# AUDIO_CODEC.net
KiCad netlist of a schematic drawn in Altium Designer
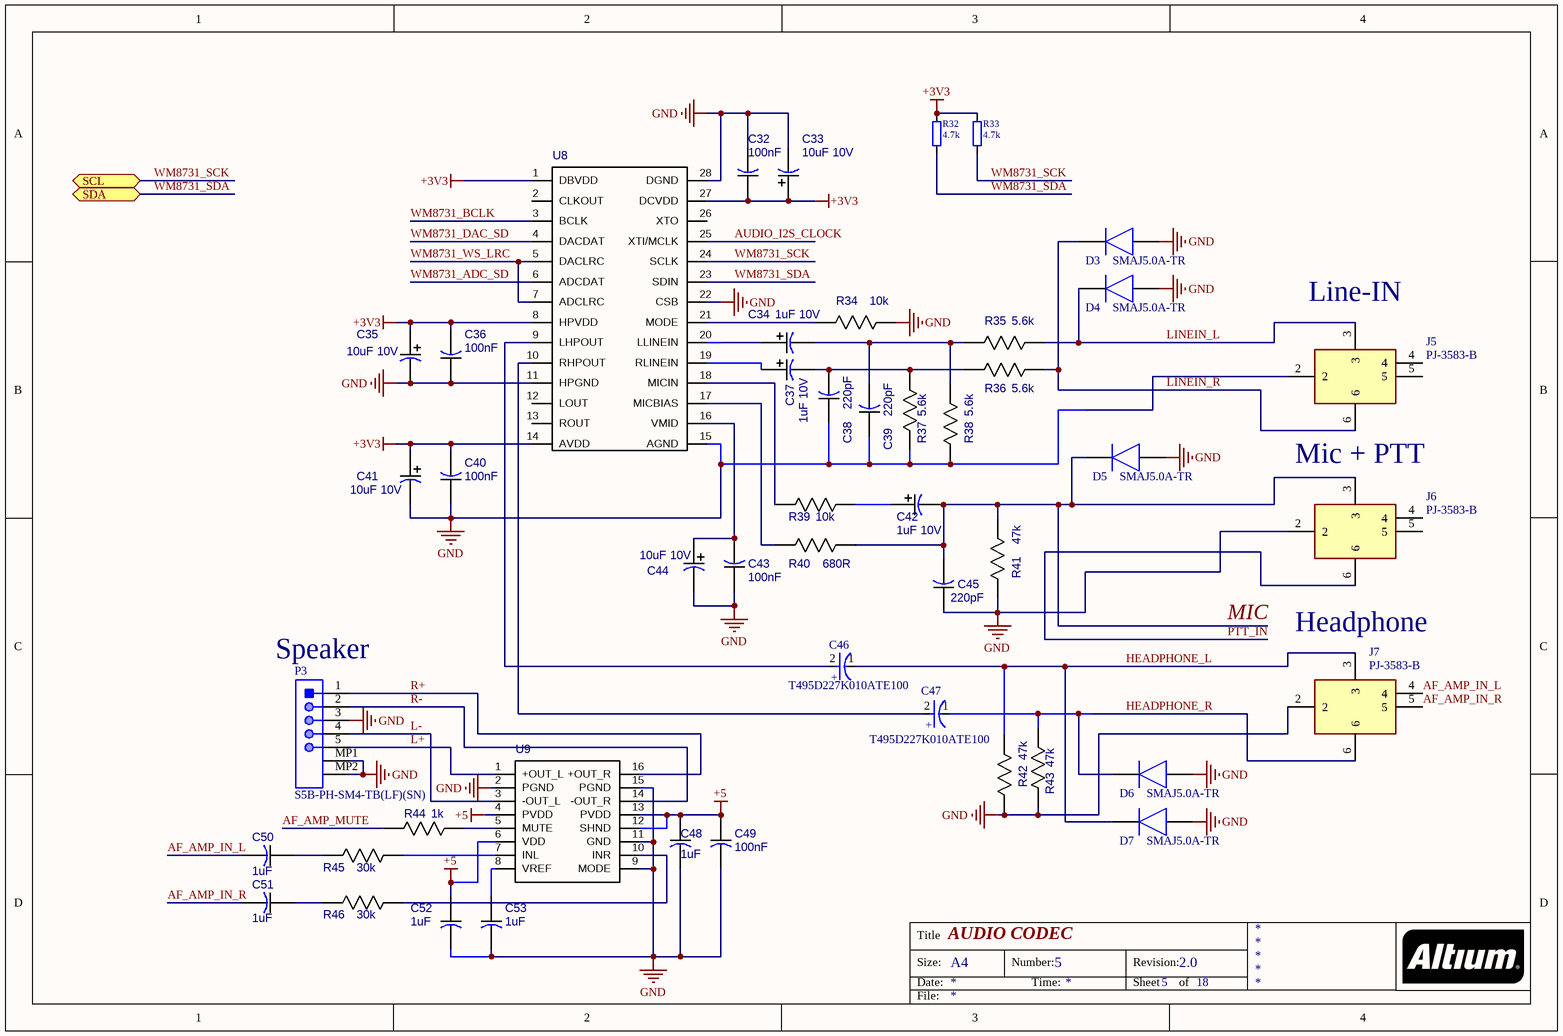
[diagram p0: AUDIO CODEC.SchDoc]

(export (version "E")
  (design (tool "Eeschema 10.0.6"))
  (components
    (comp (ref "C32")
      (value "100nF")
      (footprint "CAP_0805")
      (description "CAP_0805")
      (libsource (lib "*") (part "CAP_0805"))
    )
    (comp (ref "C33")
      (value "10uF 10V")
      (footprint "CAPAE_4.3x4.3h5.4")
      (description "CAPAE_4.3x4.3h5.4")
      (libsource (lib "*") (part "CAPAE_4.3x4.3h5.4"))
    )
    (comp (ref "C34")
      (value "1uF 10V")
      (footprint "CAPAE_4.3x4.3h5.4")
      (description "CAPAE_4.3x4.3h5.4")
      (libsource (lib "*") (part "CAPAE_4.3x4.3h5.4"))
    )
    (comp (ref "C35")
      (value "10uF 10V")
      (footprint "CAPAE_4.3x4.3h5.4")
      (description "CAPAE_4.3x4.3h5.4")
      (libsource (lib "*") (part "CAPAE_4.3x4.3h5.4"))
    )
    (comp (ref "C36")
      (value "100nF")
      (footprint "CAP_0805")
      (description "CAP_0805")
      (libsource (lib "*") (part "CAP_0805"))
    )
    (comp (ref "C37")
      (value "1uF 10V")
      (footprint "CAPAE_4.3x4.3h5.4")
      (description "CAPAE_4.3x4.3h5.4")
      (libsource (lib "*") (part "CAPAE_4.3x4.3h5.4"))
    )
    (comp (ref "C38")
      (value "220pF")
      (footprint "CAP_0805")
      (description "CAP_0805")
      (libsource (lib "*") (part "CAP_0805"))
    )
    (comp (ref "C39")
      (value "220pF")
      (footprint "CAP_0805")
      (description "CAP_0805")
      (libsource (lib "*") (part "CAP_0805"))
    )
    (comp (ref "C40")
      (value "100nF")
      (footprint "CAP_0805")
      (description "CAP_0805")
      (libsource (lib "*") (part "CAP_0805"))
    )
    (comp (ref "C41")
      (value "10uF 10V")
      (footprint "CAPAE_4.3x4.3h5.4")
      (description "CAPAE_4.3x4.3h5.4")
      (libsource (lib "*") (part "CAPAE_4.3x4.3h5.4"))
    )
    (comp (ref "C42")
      (value "1uF 10V")
      (footprint "CAPAE_4.3x4.3h5.4")
      (description "CAPAE_4.3x4.3h5.4")
      (libsource (lib "*") (part "CAPAE_4.3x4.3h5.4"))
    )
    (comp (ref "C43")
      (value "100nF")
      (footprint "CAP_0805")
      (description "CAP_0805")
      (libsource (lib "*") (part "CAP_0805"))
    )
    (comp (ref "C44")
      (value "10uF 10V")
      (footprint "CAPAE_4.3x4.3h5.4")
      (description "CAPAE_4.3x4.3h5.4")
      (libsource (lib "*") (part "CAPAE_4.3x4.3h5.4"))
    )
    (comp (ref "C45")
      (value "220pF")
      (footprint "CAP_0805")
      (description "CAP_0805")
      (libsource (lib "*") (part "CAP_0805"))
    )
    (comp (ref "C46")
      (value "T495D227K010ATE100")
      (footprint "FP-T495D227K010ATE100-MFG")
      (description "CAP TANT 220UF 10% 10V 2917")
      (fields (field (name "TOLERANCE") "10%") (field (name "VOLTAGE") "10V"))
      (libsource (lib "Altium Content Vault") (part "203bc49f2ac43e59fd269a8c329ed05"))
    )
    (comp (ref "C47")
      (value "T495D227K010ATE100")
      (footprint "FP-T495D227K010ATE100-MFG")
      (description "CAP TANT 220UF 10% 10V 2917")
      (fields (field (name "TOLERANCE") "10%") (field (name "VOLTAGE") "10V"))
      (libsource (lib "Altium Content Vault") (part "203bc49f2ac43e59fd269a8c329ed05"))
    )
    (comp (ref "C48")
      (value "1uF")
      (footprint "CAP_0805")
      (description "CAP_0805")
      (libsource (lib "*") (part "CAP_0805"))
    )
    (comp (ref "C49")
      (value "100nF")
      (footprint "CAP_0805")
      (description "CAP_0805")
      (libsource (lib "*") (part "CAP_0805"))
    )
    (comp (ref "C50")
      (value "1uF")
      (footprint "CAP_0805")
      (description "CAP_0805")
      (libsource (lib "*") (part "CAP_0805"))
    )
    (comp (ref "C51")
      (value "1uF")
      (footprint "CAP_0805")
      (description "CAP_0805")
      (libsource (lib "*") (part "CAP_0805"))
    )
    (comp (ref "C52")
      (value "1uF")
      (footprint "CAP_0805")
      (description "CAP_0805")
      (libsource (lib "*") (part "CAP_0805"))
    )
    (comp (ref "C53")
      (value "1uF")
      (footprint "CAP_0805")
      (description "CAP_0805")
      (libsource (lib "*") (part "CAP_0805"))
    )
    (comp (ref "D3")
      (value "SMAJ5.0A-TR")
      (footprint "SMBJ36CATR")
      (description "Diode")
      (fields
        (field (name "MANUFACTURER_PART_NUMBER") "SMLVT3V3")
        (field (name "MOUSER PART NUMBER") "511-SMLVT3V3")
      )
      (libsource (lib "FRONT-UNIT-7") (part "SMLVT3V3"))
    )
    (comp (ref "D4")
      (value "SMAJ5.0A-TR")
      (footprint "SMBJ36CATR")
      (description "Diode")
      (fields
        (field (name "MANUFACTURER_PART_NUMBER") "SMLVT3V3")
        (field (name "MOUSER PART NUMBER") "511-SMLVT3V3")
      )
      (libsource (lib "FRONT-UNIT-7") (part "SMLVT3V3"))
    )
    (comp (ref "D5")
      (value "SMAJ5.0A-TR")
      (footprint "SMBJ36CATR")
      (description "Diode")
      (fields
        (field (name "MANUFACTURER_PART_NUMBER") "SMLVT3V3")
        (field (name "MOUSER PART NUMBER") "511-SMLVT3V3")
      )
      (libsource (lib "FRONT-UNIT-7") (part "SMLVT3V3"))
    )
    (comp (ref "D6")
      (value "SMAJ5.0A-TR")
      (footprint "SMBJ36CATR")
      (description "Diode")
      (fields
        (field (name "MANUFACTURER_PART_NUMBER") "SMLVT3V3")
        (field (name "MOUSER PART NUMBER") "511-SMLVT3V3")
      )
      (libsource (lib "FRONT-UNIT-7") (part "SMLVT3V3"))
    )
    (comp (ref "D7")
      (value "SMAJ5.0A-TR")
      (footprint "SMBJ36CATR")
      (description "Diode")
      (fields
        (field (name "MANUFACTURER_PART_NUMBER") "SMLVT3V3")
        (field (name "MOUSER PART NUMBER") "511-SMLVT3V3")
      )
      (libsource (lib "FRONT-UNIT-7") (part "SMLVT3V3"))
    )
    (comp (ref "J5")
      (value "PJ-3583-B")
      (footprint "SamacSys:PJ3583B")
      (description "Connector")
      (libsource (lib "*") (part "PJ-3583-B"))
    )
    (comp (ref "J6")
      (value "PJ-3583-B")
      (footprint "SamacSys:PJ3583B")
      (description "Connector")
      (libsource (lib "*") (part "PJ-3583-B"))
    )
    (comp (ref "J7")
      (value "PJ-3583-B")
      (footprint "SamacSys:PJ3583B")
      (description "Connector")
      (libsource (lib "*") (part "PJ-3583-B"))
    )
    (comp (ref "P3")
      (value "S5B-PH-SM4-TB(LF)(SN)")
      (footprint "JST-S5B-PH-SM4-TB_V")
      (description "Male Header, Pitch 2 mm, 1 x 5 Position, Height 5.5 mm, -25 to 85 degC, RoHS, Tape and Reel")
      (fields (field (name "MANUFACTURER") "JST"))
      (libsource (lib "Altium Content Vault") (part "CN-1P-2M-R5"))
    )
    (comp (ref "R32")
      (value "4.7k")
      (footprint "R-0805")
      (description "Chip Resistor")
      (fields (field (name "MANUFACTURER") "Yageo/Phycomp"))
      (libsource (lib "Hristo") (part "RES semi"))
    )
    (comp (ref "R33")
      (value "4.7k")
      (footprint "R-0805")
      (description "Chip Resistor")
      (fields (field (name "MANUFACTURER") "Yageo/Phycomp"))
      (libsource (lib "Hristo") (part "RES semi"))
    )
    (comp (ref "R34")
      (value "10k")
      (footprint "RES_0805")
      (description "RES_0805")
      (libsource (lib "*") (part "RES_0805"))
    )
    (comp (ref "R35")
      (value "5.6k")
      (footprint "RES_0805")
      (description "RES_0805")
      (libsource (lib "*") (part "RES_0805"))
    )
    (comp (ref "R36")
      (value "5.6k")
      (footprint "RES_0805")
      (description "RES_0805")
      (libsource (lib "*") (part "RES_0805"))
    )
    (comp (ref "R37")
      (value "5.6k")
      (footprint "RES_0805")
      (description "RES_0805")
      (libsource (lib "*") (part "RES_0805"))
    )
    (comp (ref "R38")
      (value "5.6k")
      (footprint "RES_0805")
      (description "RES_0805")
      (libsource (lib "*") (part "RES_0805"))
    )
    (comp (ref "R39")
      (value "10k")
      (footprint "RES_0805")
      (description "RES_0805")
      (libsource (lib "*") (part "RES_0805"))
    )
    (comp (ref "R40")
      (value "680R")
      (footprint "RES_0805")
      (description "RES_0805")
      (libsource (lib "*") (part "RES_0805"))
    )
    (comp (ref "R41")
      (value "47k")
      (footprint "RES_0805")
      (description "RES_0805")
      (libsource (lib "*") (part "RES_0805"))
    )
    (comp (ref "R42")
      (value "47k")
      (footprint "RES_0805")
      (description "RES_0805")
      (libsource (lib "*") (part "RES_0805"))
    )
    (comp (ref "R43")
      (value "47k")
      (footprint "RES_0805")
      (description "RES_0805")
      (libsource (lib "*") (part "RES_0805"))
    )
    (comp (ref "R44")
      (value "1k")
      (footprint "RES_0805")
      (description "RES_0805")
      (libsource (lib "*") (part "RES_0805"))
    )
    (comp (ref "R45")
      (value "30k")
      (footprint "RES_0805")
      (description "RES_0805")
      (libsource (lib "*") (part "RES_0805"))
    )
    (comp (ref "R46")
      (value "30k")
      (footprint "RES_0805")
      (description "RES_0805")
      (libsource (lib "*") (part "RES_0805"))
    )
    (comp (ref "U8") (value "WM8731") (footprint "WM8731") (libsource (lib "FRONT-UNIT-7") (part "WM8731")))
    (comp (ref "U9")
      (value "PAM8406")
      (footprint "PAM8403")
      (libsource (lib "FRONT-UNIT-7") (part "PAM8406"))
    )
  )
  (nets
    (net (code "1") (name "+3V3") (class "Default")
      (node (ref "C32") (pin "1") (pinfunction "1_1") (pintype "passive"))
      (node (ref "C33") (pin "1") (pinfunction "PLUS_1") (pintype "passive"))
      (node (ref "C35") (pin "1") (pinfunction "PLUS_1") (pintype "passive"))
      (node (ref "C36") (pin "2") (pinfunction "2_2") (pintype "passive"))
      (node (ref "C40") (pin "2") (pinfunction "2_2") (pintype "passive"))
      (node (ref "C41") (pin "1") (pinfunction "PLUS_1") (pintype "passive"))
      (node (ref "R32") (pin "2") (pinfunction "2_2") (pintype "passive"))
      (node (ref "R33") (pin "2") (pinfunction "2_2") (pintype "passive"))
      (node (ref "U8") (pin "1") (pinfunction "DBVDD_1") (pintype "passive"))
      (node (ref "U8") (pin "14") (pinfunction "AVDD_14") (pintype "passive"))
      (node (ref "U8") (pin "27") (pinfunction "DCVDD_27") (pintype "passive"))
      (node (ref "U8") (pin "8") (pinfunction "HPVDD_8") (pintype "passive"))
    )
    (net (code "2") (name "+5") (class "Default")
      (node (ref "C48") (pin "1") (pinfunction "1_1") (pintype "passive"))
      (node (ref "C49") (pin "1") (pinfunction "1_1") (pintype "passive"))
      (node (ref "C52") (pin "1") (pinfunction "1_1") (pintype "passive"))
      (node (ref "U9") (pin "12") (pinfunction "SHND_12") (pintype "passive"))
      (node (ref "U9") (pin "13") (pinfunction "PVDD_13") (pintype "passive"))
      (node (ref "U9") (pin "4") (pinfunction "PVDD_4") (pintype "passive"))
      (node (ref "U9") (pin "6") (pinfunction "VDD_6") (pintype "passive"))
    )
    (net (code "3") (name "/AF_AMP_IN_L") (class "Default")
      (node (ref "C50") (pin "2") (pinfunction "2_2") (pintype "passive"))
      (node (ref "J7") (pin "4") (pinfunction "4_4") (pintype "passive"))
    )
    (net (code "4") (name "/AF_AMP_IN_R") (class "Default")
      (node (ref "C51") (pin "2") (pinfunction "2_2") (pintype "passive"))
      (node (ref "J7") (pin "5") (pinfunction "5_5") (pintype "passive"))
    )
    (net (code "5") (name "/AF_AMP_MUTE") (class "Default")
      (node (ref "R44") (pin "2") (pinfunction "2_2") (pintype "passive"))
    )
    (net (code "6") (name "/AUDIO_I2S_CLOCK") (class "Default")
      (node (ref "U8") (pin "25") (pinfunction "XTI/MCLK_25") (pintype "passive"))
    )
    (net (code "7") (name "/HEADPHONE_L") (class "Default")
      (node (ref "C46") (pin "1") (pinfunction "C_1") (pintype "passive"))
      (node (ref "D7") (pin "1") (pinfunction "K_1") (pintype "passive"))
      (node (ref "J7") (pin "3") (pinfunction "3_3") (pintype "passive"))
      (node (ref "R42") (pin "2") (pinfunction "2_2") (pintype "passive"))
    )
    (net (code "8") (name "/HEADPHONE_R") (class "Default")
      (node (ref "C47") (pin "1") (pinfunction "C_1") (pintype "passive"))
      (node (ref "D6") (pin "1") (pinfunction "K_1") (pintype "passive"))
      (node (ref "J7") (pin "6") (pinfunction "6_6") (pintype "passive"))
      (node (ref "R43") (pin "2") (pinfunction "2_2") (pintype "passive"))
    )
    (net (code "9") (name "/L+") (class "Default")
      (node (ref "P3") (pin "5") (pinfunction "5_5") (pintype "passive"))
      (node (ref "U9") (pin "1") (pinfunction "+OUT_L_1") (pintype "passive"))
    )
    (net (code "10") (name "/L-") (class "Default")
      (node (ref "P3") (pin "4") (pinfunction "4_4") (pintype "passive"))
      (node (ref "U9") (pin "3") (pinfunction "-OUT_L_3") (pintype "passive"))
    )
    (net (code "11") (name "/LINEIN_L") (class "Default")
      (node (ref "D4") (pin "1") (pinfunction "K_1") (pintype "passive"))
      (node (ref "J5") (pin "3") (pinfunction "3_3") (pintype "passive"))
      (node (ref "R35") (pin "1") (pinfunction "1_1") (pintype "passive"))
    )
    (net (code "12") (name "/LINEIN_R") (class "Default")
      (node (ref "D3") (pin "1") (pinfunction "K_1") (pintype "passive"))
      (node (ref "J5") (pin "6") (pinfunction "6_6") (pintype "passive"))
      (node (ref "R36") (pin "1") (pinfunction "1_1") (pintype "passive"))
    )
    (net (code "13") (name "/MIC") (class "Default")
      (node (ref "C42") (pin "2") (pinfunction "MINUS_2") (pintype "passive"))
      (node (ref "C45") (pin "2") (pinfunction "2_2") (pintype "passive"))
      (node (ref "D5") (pin "1") (pinfunction "K_1") (pintype "passive"))
      (node (ref "J6") (pin "3") (pinfunction "3_3") (pintype "passive"))
      (node (ref "R40") (pin "1") (pinfunction "1_1") (pintype "passive"))
      (node (ref "R41") (pin "2") (pinfunction "2_2") (pintype "passive"))
    )
    (net (code "14") (name "/PTT_IN") (class "Default")
      (node (ref "J6") (pin "6") (pinfunction "6_6") (pintype "passive"))
    )
    (net (code "15") (name "/R+") (class "Default")
      (node (ref "P3") (pin "1") (pinfunction "1_1") (pintype "passive"))
      (node (ref "U9") (pin "16") (pinfunction "+OUT_R_16") (pintype "passive"))
    )
    (net (code "16") (name "/R-") (class "Default")
      (node (ref "P3") (pin "2") (pinfunction "2_2") (pintype "passive"))
      (node (ref "U9") (pin "14") (pinfunction "-OUT_R_14") (pintype "passive"))
    )
    (net (code "17") (name "/WM8731_ADC_SD") (class "Default")
      (node (ref "U8") (pin "6") (pinfunction "ADCDAT_6") (pintype "passive"))
    )
    (net (code "18") (name "/WM8731_BCLK") (class "Default")
      (node (ref "U8") (pin "3") (pinfunction "BCLK_3") (pintype "passive"))
    )
    (net (code "19") (name "/WM8731_DAC_SD") (class "Default")
      (node (ref "U8") (pin "4") (pinfunction "DACDAT_4") (pintype "passive"))
    )
    (net (code "20") (name "/WM8731_SCK") (class "Default")
      (node (ref "R33") (pin "1") (pinfunction "1_1") (pintype "passive"))
      (node (ref "U8") (pin "24") (pinfunction "SCLK_24") (pintype "passive"))
    )
    (net (code "21") (name "/WM8731_SDA") (class "Default")
      (node (ref "R32") (pin "1") (pinfunction "1_1") (pintype "passive"))
      (node (ref "U8") (pin "23") (pinfunction "SDIN_23") (pintype "passive"))
    )
    (net (code "22") (name "/WM8731_WS_LRC") (class "Default")
      (node (ref "U8") (pin "5") (pinfunction "DACLRC_5") (pintype "passive"))
      (node (ref "U8") (pin "7") (pinfunction "ADCLRC_7") (pintype "passive"))
    )
    (net (code "23") (name "GND") (class "Default")
      (node (ref "C32") (pin "2") (pinfunction "2_2") (pintype "passive"))
      (node (ref "C33") (pin "2") (pinfunction "MINUS_2") (pintype "passive"))
      (node (ref "C35") (pin "2") (pinfunction "MINUS_2") (pintype "passive"))
      (node (ref "C36") (pin "1") (pinfunction "1_1") (pintype "passive"))
      (node (ref "C38") (pin "1") (pinfunction "1_1") (pintype "passive"))
      (node (ref "C39") (pin "1") (pinfunction "1_1") (pintype "passive"))
      (node (ref "C40") (pin "1") (pinfunction "1_1") (pintype "passive"))
      (node (ref "C41") (pin "2") (pinfunction "MINUS_2") (pintype "passive"))
      (node (ref "C43") (pin "1") (pinfunction "1_1") (pintype "passive"))
      (node (ref "C44") (pin "2") (pinfunction "MINUS_2") (pintype "passive"))
      (node (ref "C45") (pin "1") (pinfunction "1_1") (pintype "passive"))
      (node (ref "C48") (pin "2") (pinfunction "2_2") (pintype "passive"))
      (node (ref "C49") (pin "2") (pinfunction "2_2") (pintype "passive"))
      (node (ref "C52") (pin "2") (pinfunction "2_2") (pintype "passive"))
      (node (ref "C53") (pin "2") (pinfunction "2_2") (pintype "passive"))
      (node (ref "D3") (pin "2") (pinfunction "A_2") (pintype "passive"))
      (node (ref "D4") (pin "2") (pinfunction "A_2") (pintype "passive"))
      (node (ref "D5") (pin "2") (pinfunction "A_2") (pintype "passive"))
      (node (ref "D6") (pin "2") (pinfunction "A_2") (pintype "passive"))
      (node (ref "D7") (pin "2") (pinfunction "A_2") (pintype "passive"))
      (node (ref "J5") (pin "2") (pinfunction "2_2") (pintype "passive"))
      (node (ref "J6") (pin "2") (pinfunction "2_2") (pintype "passive"))
      (node (ref "J7") (pin "2") (pinfunction "2_2") (pintype "passive"))
      (node (ref "P3") (pin "3") (pinfunction "3_3") (pintype "passive"))
      (node (ref "P3") (pin "MP1") (pinfunction "MP1_MP1") (pintype "passive"))
      (node (ref "P3") (pin "MP2") (pinfunction "MP2_MP2") (pintype "passive"))
      (node (ref "R34") (pin "1") (pinfunction "1_1") (pintype "passive"))
      (node (ref "R37") (pin "1") (pinfunction "1_1") (pintype "passive"))
      (node (ref "R38") (pin "1") (pinfunction "1_1") (pintype "passive"))
      (node (ref "R41") (pin "1") (pinfunction "1_1") (pintype "passive"))
      (node (ref "R42") (pin "1") (pinfunction "1_1") (pintype "passive"))
      (node (ref "R43") (pin "1") (pinfunction "1_1") (pintype "passive"))
      (node (ref "U8") (pin "11") (pinfunction "HPGND_11") (pintype "passive"))
      (node (ref "U8") (pin "15") (pinfunction "AGND_15") (pintype "passive"))
      (node (ref "U8") (pin "22") (pinfunction "CSB_22") (pintype "passive"))
      (node (ref "U8") (pin "28") (pinfunction "DGND_28") (pintype "passive"))
      (node (ref "U9") (pin "11") (pinfunction "GND_11") (pintype "passive"))
      (node (ref "U9") (pin "15") (pinfunction "PGND_15") (pintype "passive"))
      (node (ref "U9") (pin "2") (pinfunction "PGND_2") (pintype "passive"))
      (node (ref "U9") (pin "9") (pinfunction "MODE_9") (pintype "passive"))
    )
    (net (code "24") (name "Net-(C34-MINUS)") (class "Default")
      (node (ref "C34") (pin "2") (pinfunction "MINUS_2") (pintype "passive"))
      (node (ref "C39") (pin "2") (pinfunction "2_2") (pintype "passive"))
      (node (ref "R35") (pin "2") (pinfunction "2_2") (pintype "passive"))
      (node (ref "R38") (pin "2") (pinfunction "2_2") (pintype "passive"))
    )
    (net (code "25") (name "Net-(C34-PLUS)") (class "Default")
      (node (ref "C34") (pin "1") (pinfunction "PLUS_1") (pintype "passive"))
      (node (ref "U8") (pin "20") (pinfunction "LLINEIN_20") (pintype "passive"))
    )
    (net (code "26") (name "Net-(C37-MINUS)") (class "Default")
      (node (ref "C37") (pin "2") (pinfunction "MINUS_2") (pintype "passive"))
      (node (ref "C38") (pin "2") (pinfunction "2_2") (pintype "passive"))
      (node (ref "R36") (pin "2") (pinfunction "2_2") (pintype "passive"))
      (node (ref "R37") (pin "2") (pinfunction "2_2") (pintype "passive"))
    )
    (net (code "27") (name "Net-(C37-PLUS)") (class "Default")
      (node (ref "C37") (pin "1") (pinfunction "PLUS_1") (pintype "passive"))
      (node (ref "U8") (pin "19") (pinfunction "RLINEIN_19") (pintype "passive"))
    )
    (net (code "28") (name "Net-(C42-PLUS)") (class "Default")
      (node (ref "C42") (pin "1") (pinfunction "PLUS_1") (pintype "passive"))
      (node (ref "R39") (pin "1") (pinfunction "1_1") (pintype "passive"))
    )
    (net (code "29") (name "Net-(C44-PLUS)") (class "Default")
      (node (ref "C43") (pin "2") (pinfunction "2_2") (pintype "passive"))
      (node (ref "C44") (pin "1") (pinfunction "PLUS_1") (pintype "passive"))
      (node (ref "U8") (pin "16") (pinfunction "VMID_16") (pintype "passive"))
    )
    (net (code "30") (name "Net-(C46-A)") (class "Default")
      (node (ref "C46") (pin "2") (pinfunction "A_2") (pintype "passive"))
      (node (ref "U8") (pin "9") (pinfunction "LHPOUT_9") (pintype "passive"))
    )
    (net (code "31") (name "Net-(C47-A)") (class "Default")
      (node (ref "C47") (pin "2") (pinfunction "A_2") (pintype "passive"))
      (node (ref "U8") (pin "10") (pinfunction "RHPOUT_10") (pintype "passive"))
    )
    (net (code "32") (name "Net-(C50-Pad1)") (class "Default")
      (node (ref "C50") (pin "1") (pinfunction "1_1") (pintype "passive"))
      (node (ref "R45") (pin "2") (pinfunction "2_2") (pintype "passive"))
    )
    (net (code "33") (name "Net-(C51-Pad1)") (class "Default")
      (node (ref "C51") (pin "1") (pinfunction "1_1") (pintype "passive"))
      (node (ref "R46") (pin "2") (pinfunction "2_2") (pintype "passive"))
    )
    (net (code "34") (name "Net-(U8-MICBIAS)") (class "Default")
      (node (ref "R40") (pin "2") (pinfunction "2_2") (pintype "passive"))
      (node (ref "U8") (pin "17") (pinfunction "MICBIAS_17") (pintype "passive"))
    )
    (net (code "35") (name "Net-(U8-MICIN)") (class "Default")
      (node (ref "R39") (pin "2") (pinfunction "2_2") (pintype "passive"))
      (node (ref "U8") (pin "18") (pinfunction "MICIN_18") (pintype "passive"))
    )
    (net (code "36") (name "Net-(U8-MODE)") (class "Default")
      (node (ref "R34") (pin "2") (pinfunction "2_2") (pintype "passive"))
      (node (ref "U8") (pin "21") (pinfunction "MODE_21") (pintype "passive"))
    )
    (net (code "37") (name "Net-(U9-INL)") (class "Default")
      (node (ref "R45") (pin "1") (pinfunction "1_1") (pintype "passive"))
      (node (ref "U9") (pin "7") (pinfunction "INL_7") (pintype "passive"))
    )
    (net (code "38") (name "Net-(U9-INR)") (class "Default")
      (node (ref "R46") (pin "1") (pinfunction "1_1") (pintype "passive"))
      (node (ref "U9") (pin "10") (pinfunction "INR_10") (pintype "passive"))
    )
    (net (code "39") (name "Net-(U9-MUTE)") (class "Default")
      (node (ref "R44") (pin "1") (pinfunction "1_1") (pintype "passive"))
      (node (ref "U9") (pin "5") (pinfunction "MUTE_5") (pintype "passive"))
    )
    (net (code "40") (name "Net-(U9-VREF)") (class "Default")
      (node (ref "C53") (pin "1") (pinfunction "1_1") (pintype "passive"))
      (node (ref "U9") (pin "8") (pinfunction "VREF_8") (pintype "passive"))
    )
    (net (code "41") (name "unconnected-(J5-Pad4)") (class "Default")
      (node (ref "J5") (pin "4") (pinfunction "4_4") (pintype "passive"))
    )
    (net (code "42") (name "unconnected-(J5-Pad5)") (class "Default")
      (node (ref "J5") (pin "5") (pinfunction "5_5") (pintype "passive"))
    )
    (net (code "43") (name "unconnected-(J6-Pad4)") (class "Default")
      (node (ref "J6") (pin "4") (pinfunction "4_4") (pintype "passive"))
    )
    (net (code "44") (name "unconnected-(J6-Pad5)") (class "Default")
      (node (ref "J6") (pin "5") (pinfunction "5_5") (pintype "passive"))
    )
    (net (code "45") (name "unconnected-(U8-CLKOUT-Pad2)") (class "Default")
      (node (ref "U8") (pin "2") (pinfunction "CLKOUT_2") (pintype "passive"))
    )
    (net (code "46") (name "unconnected-(U8-LOUT-Pad12)") (class "Default")
      (node (ref "U8") (pin "12") (pinfunction "LOUT_12") (pintype "passive"))
    )
    (net (code "47") (name "unconnected-(U8-ROUT-Pad13)") (class "Default")
      (node (ref "U8") (pin "13") (pinfunction "ROUT_13") (pintype "passive"))
    )
    (net (code "48") (name "unconnected-(U8-XTO-Pad26)") (class "Default")
      (node (ref "U8") (pin "26") (pinfunction "XTO_26") (pintype "passive"))
    )
  )
)
